# smartclamp_v0_14.net
KiCad netlist of a schematic drawn in EAGLE
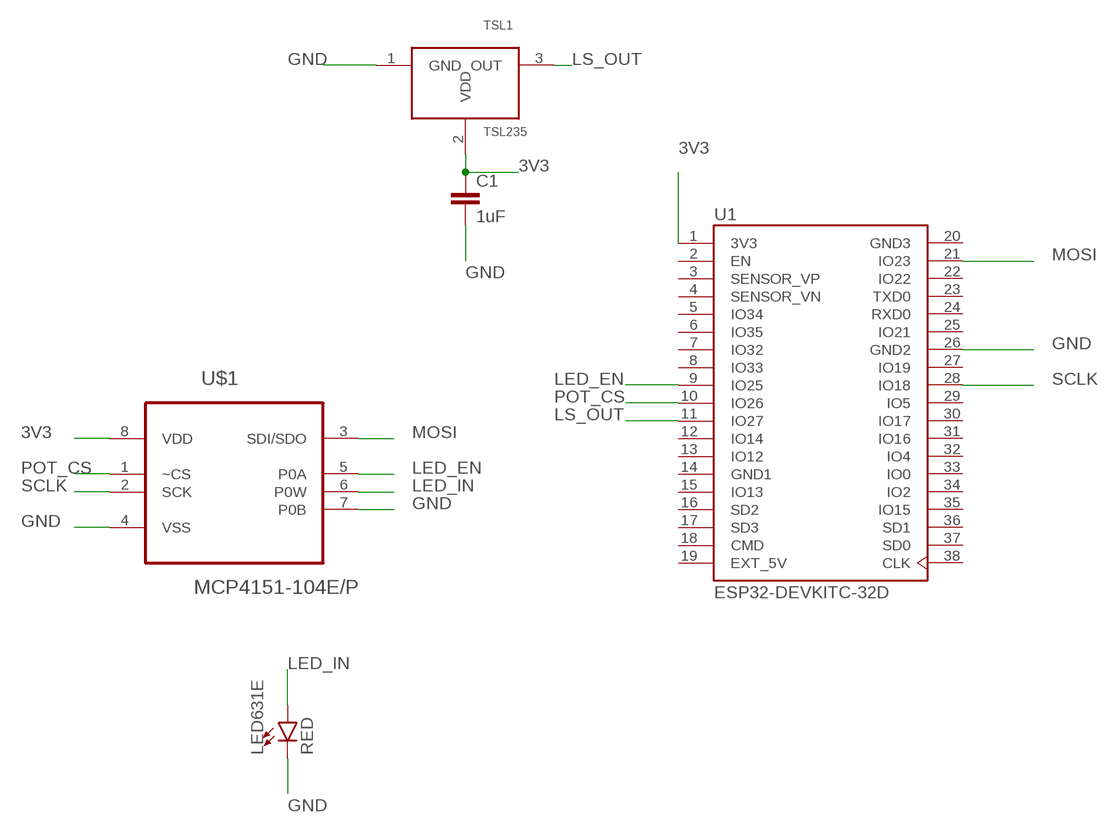
[diagram p0: schematic, sheet 1]

(export (version "E")
  (design (tool "Eeschema 10.0.6"))
  (components
    (comp (ref "C1")
      (value "1uF")
      (footprint "eagle-import:0603")
      (libsource (lib "eagle-import") (part "1.0NF/1000PF-0603-50V-10%"))
    )
    (comp (ref "LED631E")
      (value "RED")
      (footprint "eagle-import:LED-1206")
      (libsource (lib "eagle-import") (part "LED-RED1206"))
    )
    (comp (ref "TSL1")
      (value "TSL235")
      (footprint "eagle-import:TSL235-P")
      (fields (field (name "MF") "ams"))
      (libsource (lib "eagle-import") (part "TSL235"))
    )
    (comp (ref "U$1")
      (value "MCP4151-104E/P")
      (footprint "eagle-import:DIP254P762X533-8")
      (fields (field (name "MF") "Microchip"))
      (libsource (lib "eagle-import") (part "MCP4151-104E/P"))
    )
    (comp (ref "U1")
      (value "ESP32-DEVKITC-32D")
      (footprint "eagle-import:MODULE_ESP32-DEVKITC-32D")
      (fields (field (name "MF") "Espressif Systems"))
      (libsource (lib "eagle-import") (part "ESP32-DEVKITC-32D"))
    )
  )
  (nets
    (net (code "1") (name "/3V3") (class "Default")
      (node (ref "C1") (pin "1") (pinfunction "1_1") (pintype "passive"))
      (node (ref "TSL1") (pin "2") (pinfunction "VDD_2") (pintype "bidirectional"))
      (node (ref "U$1") (pin "8") (pinfunction "VDD_8") (pintype "power_in"))
      (node (ref "U1") (pin "1") (pinfunction "3V3_1") (pintype "power_in"))
    )
    (net (code "2") (name "/EXT_5V") (class "Default")
      (node (ref "U1") (pin "19") (pinfunction "EXT_5V_19") (pintype "power_in"))
    )
    (net (code "3") (name "/GND") (class "Default")
      (node (ref "C1") (pin "2") (pinfunction "2_2") (pintype "passive"))
      (node (ref "LED631E") (pin "C") (pinfunction "C_C") (pintype "passive"))
      (node (ref "TSL1") (pin "1") (pinfunction "GND_1") (pintype "bidirectional"))
      (node (ref "U$1") (pin "4") (pinfunction "VSS_4") (pintype "power_in"))
      (node (ref "U$1") (pin "7") (pinfunction "P0B_7") (pintype "passive"))
      (node (ref "U1") (pin "26") (pinfunction "GND2_26") (pintype "power_in"))
    )
    (net (code "4") (name "/GND1") (class "Default")
      (node (ref "U1") (pin "14") (pinfunction "GND1_14") (pintype "power_in"))
    )
    (net (code "5") (name "/GND3") (class "Default")
      (node (ref "U1") (pin "20") (pinfunction "GND3_20") (pintype "power_in"))
    )
    (net (code "6") (name "/LED_EN") (class "Default")
      (node (ref "U$1") (pin "5") (pinfunction "P0A_5") (pintype "passive"))
      (node (ref "U1") (pin "9") (pinfunction "IO25_9") (pintype "bidirectional"))
    )
    (net (code "7") (name "/LED_IN") (class "Default")
      (node (ref "LED631E") (pin "A") (pinfunction "A_A") (pintype "passive"))
      (node (ref "U$1") (pin "6") (pinfunction "P0W_6") (pintype "passive"))
    )
    (net (code "8") (name "/LS_OUT") (class "Default")
      (node (ref "TSL1") (pin "3") (pinfunction "OUT_3") (pintype "bidirectional"))
      (node (ref "U1") (pin "11") (pinfunction "IO27_11") (pintype "bidirectional"))
    )
    (net (code "9") (name "/MOSI") (class "Default")
      (node (ref "U$1") (pin "3") (pinfunction "SDI/SDO_3") (pintype "bidirectional"))
      (node (ref "U1") (pin "21") (pinfunction "IO23_21") (pintype "bidirectional"))
    )
    (net (code "10") (name "/POT_CS") (class "Default")
      (node (ref "U$1") (pin "1") (pinfunction "~{CS}_1") (pintype "input"))
      (node (ref "U1") (pin "10") (pinfunction "IO26_10") (pintype "bidirectional"))
    )
    (net (code "11") (name "/SCLK") (class "Default")
      (node (ref "U$1") (pin "2") (pinfunction "SCK_2") (pintype "input"))
      (node (ref "U1") (pin "28") (pinfunction "IO18_28") (pintype "bidirectional"))
    )
    (net (code "12") (name "unconnected-(U1-CLK-Pad38)") (class "Default")
      (node (ref "U1") (pin "38") (pinfunction "CLK_38") (pintype "input"))
    )
    (net (code "13") (name "unconnected-(U1-CMD-Pad18)") (class "Default")
      (node (ref "U1") (pin "18") (pinfunction "CMD_18") (pintype "bidirectional"))
    )
    (net (code "14") (name "unconnected-(U1-EN-Pad2)") (class "Default")
      (node (ref "U1") (pin "2") (pinfunction "EN_2") (pintype "input"))
    )
    (net (code "15") (name "unconnected-(U1-IO0-Pad33)") (class "Default")
      (node (ref "U1") (pin "33") (pinfunction "IO0_33") (pintype "bidirectional"))
    )
    (net (code "16") (name "unconnected-(U1-IO2-Pad34)") (class "Default")
      (node (ref "U1") (pin "34") (pinfunction "IO2_34") (pintype "bidirectional"))
    )
    (net (code "17") (name "unconnected-(U1-IO4-Pad32)") (class "Default")
      (node (ref "U1") (pin "32") (pinfunction "IO4_32") (pintype "bidirectional"))
    )
    (net (code "18") (name "unconnected-(U1-IO5-Pad29)") (class "Default")
      (node (ref "U1") (pin "29") (pinfunction "IO5_29") (pintype "bidirectional"))
    )
    (net (code "19") (name "unconnected-(U1-IO12-Pad13)") (class "Default")
      (node (ref "U1") (pin "13") (pinfunction "IO12_13") (pintype "bidirectional"))
    )
    (net (code "20") (name "unconnected-(U1-IO13-Pad15)") (class "Default")
      (node (ref "U1") (pin "15") (pinfunction "IO13_15") (pintype "bidirectional"))
    )
    (net (code "21") (name "unconnected-(U1-IO14-Pad12)") (class "Default")
      (node (ref "U1") (pin "12") (pinfunction "IO14_12") (pintype "bidirectional"))
    )
    (net (code "22") (name "unconnected-(U1-IO15-Pad35)") (class "Default")
      (node (ref "U1") (pin "35") (pinfunction "IO15_35") (pintype "bidirectional"))
    )
    (net (code "23") (name "unconnected-(U1-IO16-Pad31)") (class "Default")
      (node (ref "U1") (pin "31") (pinfunction "IO16_31") (pintype "bidirectional"))
    )
    (net (code "24") (name "unconnected-(U1-IO17-Pad30)") (class "Default")
      (node (ref "U1") (pin "30") (pinfunction "IO17_30") (pintype "bidirectional"))
    )
    (net (code "25") (name "unconnected-(U1-IO19-Pad27)") (class "Default")
      (node (ref "U1") (pin "27") (pinfunction "IO19_27") (pintype "bidirectional"))
    )
    (net (code "26") (name "unconnected-(U1-IO21-Pad25)") (class "Default")
      (node (ref "U1") (pin "25") (pinfunction "IO21_25") (pintype "bidirectional"))
    )
    (net (code "27") (name "unconnected-(U1-IO22-Pad22)") (class "Default")
      (node (ref "U1") (pin "22") (pinfunction "IO22_22") (pintype "bidirectional"))
    )
    (net (code "28") (name "unconnected-(U1-IO32-Pad7)") (class "Default")
      (node (ref "U1") (pin "7") (pinfunction "IO32_7") (pintype "bidirectional"))
    )
    (net (code "29") (name "unconnected-(U1-IO33-Pad8)") (class "Default")
      (node (ref "U1") (pin "8") (pinfunction "IO33_8") (pintype "bidirectional"))
    )
    (net (code "30") (name "unconnected-(U1-IO34-Pad5)") (class "Default")
      (node (ref "U1") (pin "5") (pinfunction "IO34_5") (pintype "bidirectional"))
    )
    (net (code "31") (name "unconnected-(U1-IO35-Pad6)") (class "Default")
      (node (ref "U1") (pin "6") (pinfunction "IO35_6") (pintype "bidirectional"))
    )
    (net (code "32") (name "unconnected-(U1-RXD0-Pad24)") (class "Default")
      (node (ref "U1") (pin "24") (pinfunction "RXD0_24") (pintype "input"))
    )
    (net (code "33") (name "unconnected-(U1-SD0-Pad37)") (class "Default")
      (node (ref "U1") (pin "37") (pinfunction "SD0_37") (pintype "bidirectional"))
    )
    (net (code "34") (name "unconnected-(U1-SD1-Pad36)") (class "Default")
      (node (ref "U1") (pin "36") (pinfunction "SD1_36") (pintype "bidirectional"))
    )
    (net (code "35") (name "unconnected-(U1-SD2-Pad16)") (class "Default")
      (node (ref "U1") (pin "16") (pinfunction "SD2_16") (pintype "bidirectional"))
    )
    (net (code "36") (name "unconnected-(U1-SD3-Pad17)") (class "Default")
      (node (ref "U1") (pin "17") (pinfunction "SD3_17") (pintype "bidirectional"))
    )
    (net (code "37") (name "unconnected-(U1-SENSOR_VN-Pad4)") (class "Default")
      (node (ref "U1") (pin "4") (pinfunction "SENSOR_VN_4") (pintype "input"))
    )
    (net (code "38") (name "unconnected-(U1-SENSOR_VP-Pad3)") (class "Default")
      (node (ref "U1") (pin "3") (pinfunction "SENSOR_VP_3") (pintype "input"))
    )
    (net (code "39") (name "unconnected-(U1-TXD0-Pad23)") (class "Default")
      (node (ref "U1") (pin "23") (pinfunction "TXD0_23") (pintype "output"))
    )
  )
)
